# Sheet1.net
KiCad netlist of a schematic drawn in Altium Designer
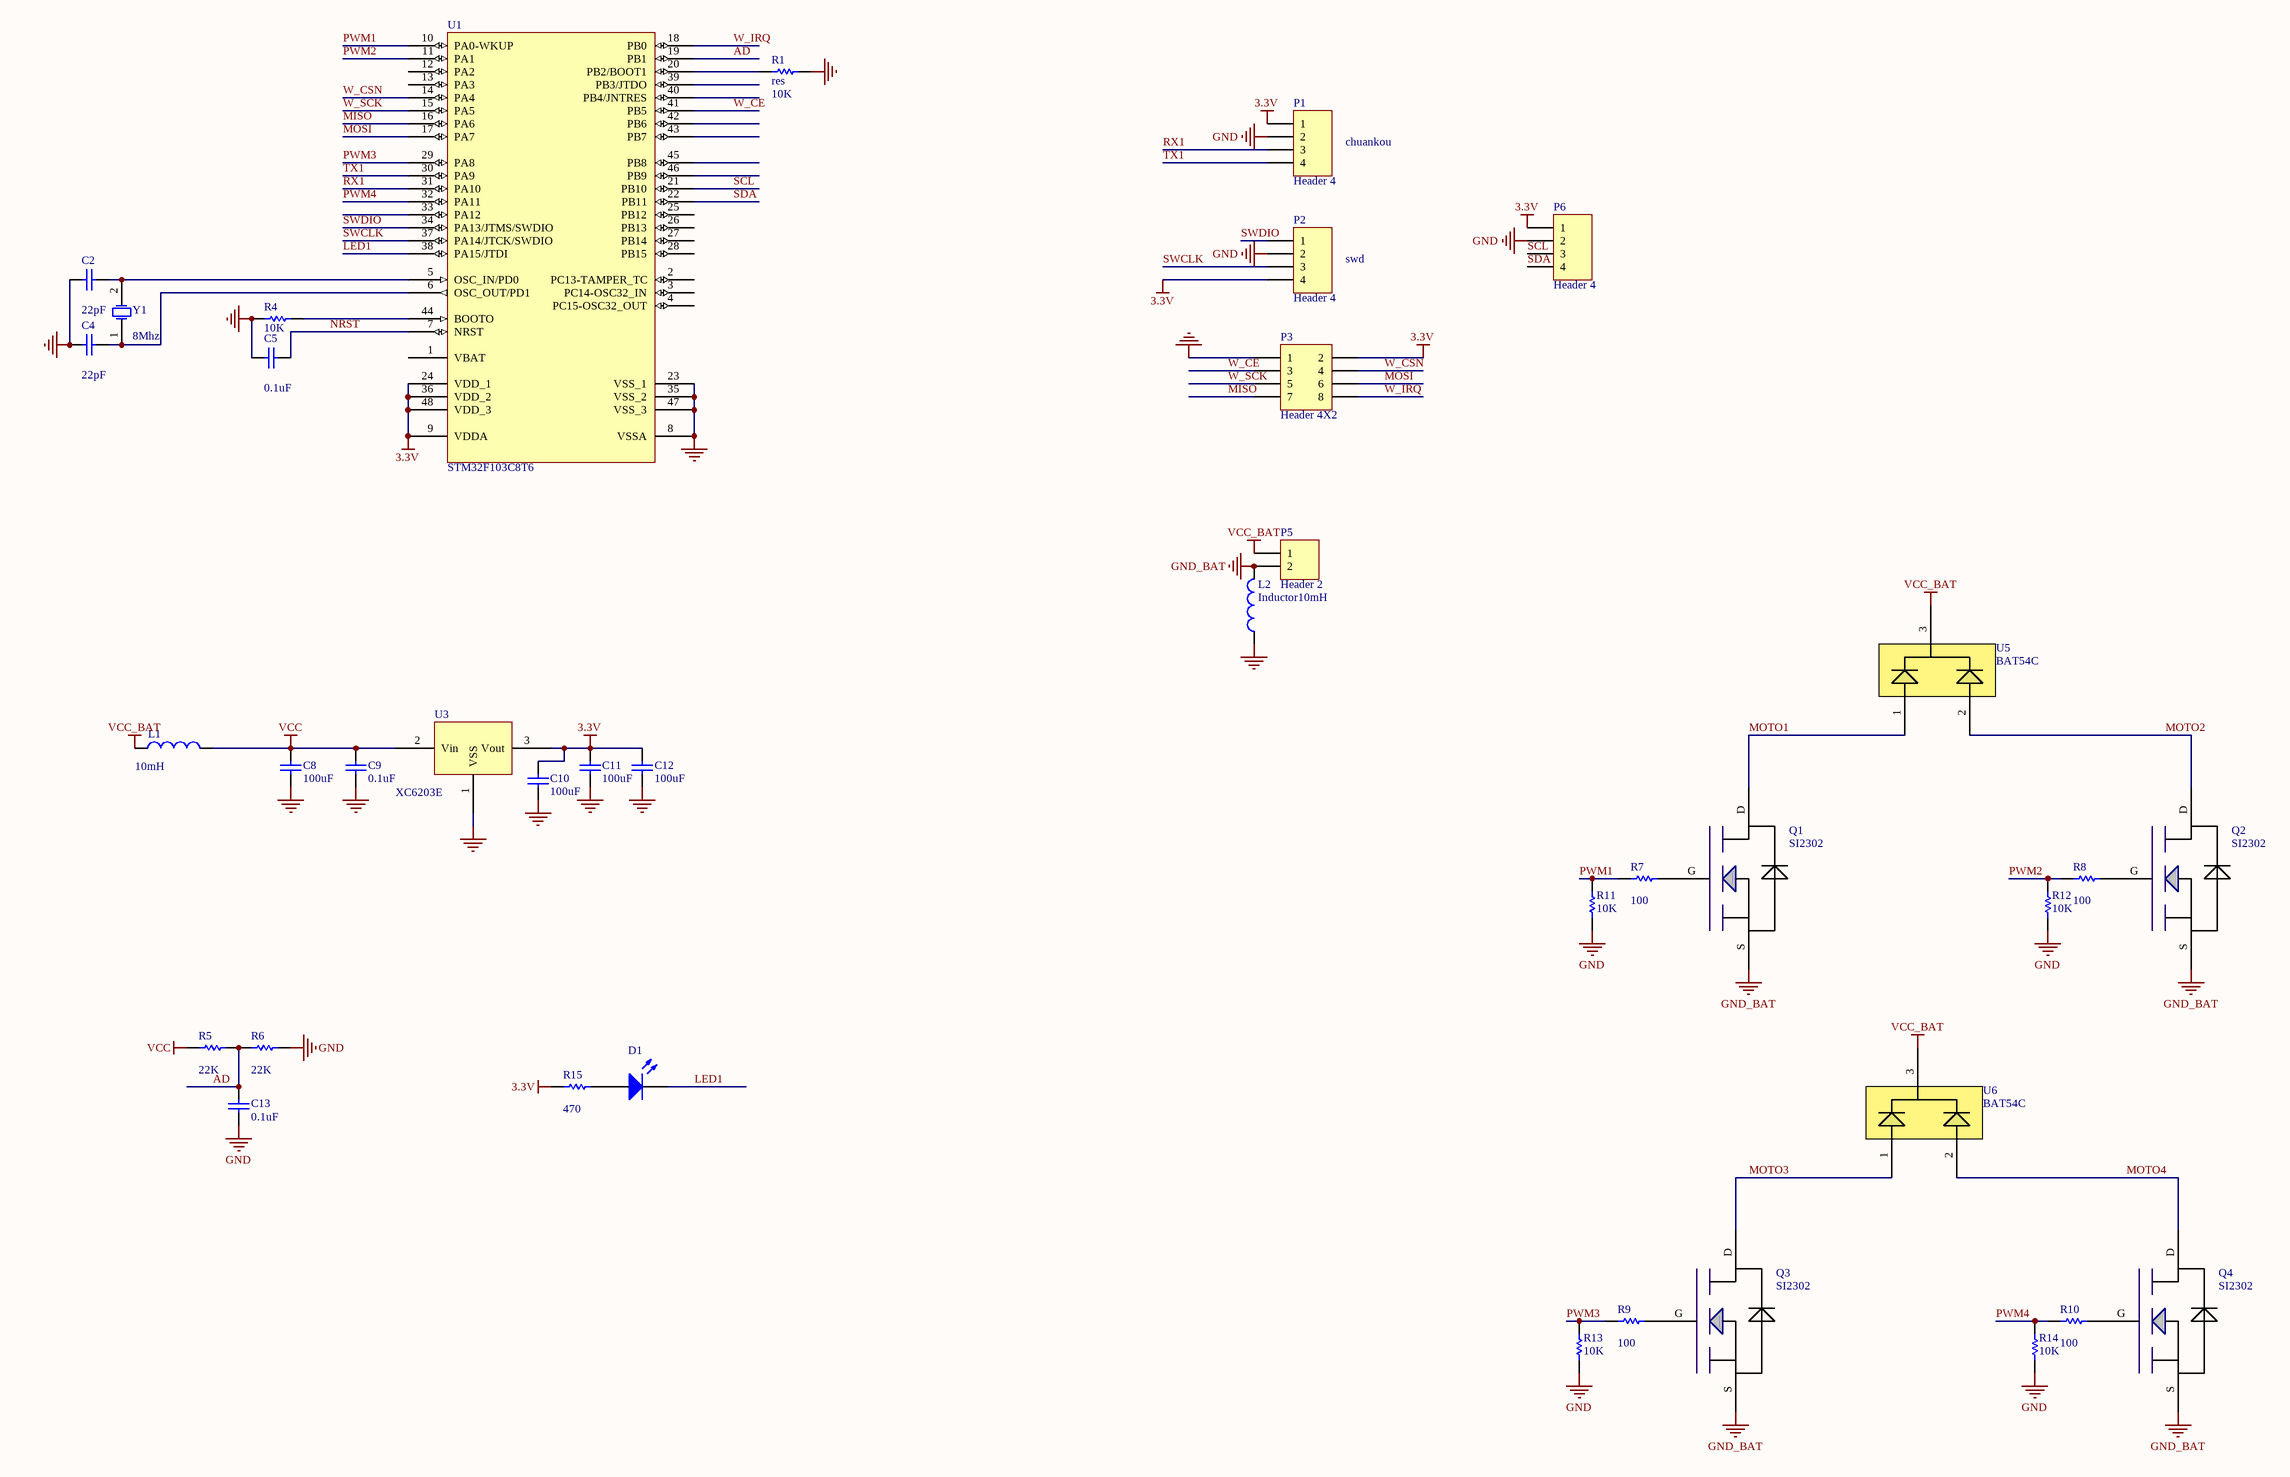
[diagram p0: Sheet1.SchDoc]

(export (version "E")
  (design (tool "Eeschema 10.0.6"))
  (components
    (comp (ref "C2")
      (value "22pF")
      (footprint "0603")
      (fields (field (name "Comment") "cap"))
      (libsource (lib "bai") (part "cap"))
    )
    (comp (ref "C4")
      (value "22pF")
      (footprint "0603")
      (fields (field (name "Comment") "cap"))
      (libsource (lib "bai") (part "cap"))
    )
    (comp (ref "C5")
      (value "0.1uF")
      (footprint "0603")
      (fields (field (name "Comment") "cap"))
      (libsource (lib "bai") (part "cap"))
    )
    (comp (ref "C8")
      (value "100uF")
      (footprint "0603")
      (fields (field (name "Comment") "cap"))
      (libsource (lib "bai") (part "cap"))
    )
    (comp (ref "C9")
      (value "0.1uF")
      (footprint "0603")
      (fields (field (name "Comment") "cap"))
      (libsource (lib "bai") (part "cap"))
    )
    (comp (ref "C10")
      (value "100uF")
      (footprint "0603")
      (fields (field (name "Comment") "cap"))
      (libsource (lib "bai") (part "cap"))
    )
    (comp (ref "C11")
      (value "100uF")
      (footprint "0603")
      (fields (field (name "Comment") "cap"))
      (libsource (lib "bai") (part "cap"))
    )
    (comp (ref "C12")
      (value "100uF")
      (footprint "0603")
      (fields (field (name "Comment") "cap"))
      (libsource (lib "bai") (part "cap"))
    )
    (comp (ref "C13")
      (value "0.1uF")
      (footprint "0603")
      (fields (field (name "Comment") "cap"))
      (libsource (lib "bai") (part "cap"))
    )
    (comp (ref "D1")
      (value "LED0")
      (footprint "0805")
      (description "Typical INFRARED GaAs LED")
      (fields (field (name "PUBLISHER") "Altium Limited"))
      (libsource (lib "Miscellaneous Devices") (part "LED0"))
    )
    (comp (ref "L1")
      (value "10mH")
      (footprint "0805")
      (fields (field (name "Comment") "Inductor"))
      (libsource (lib "bai") (part "Inductor"))
    )
    (comp (ref "L2") (value "Inductor10mH") (footprint "0805") (libsource (lib "bai") (part "Inductor")))
    (comp (ref "P1")
      (value "Header 4")
      (footprint "HDR1X4")
      (description "Header, 4-Pin")
      (fields (field (name "PUBLISHER") "Altium Limited"))
      (libsource (lib "Miscellaneous Connectors") (part "Header 4"))
    )
    (comp (ref "P2")
      (value "Header 4")
      (footprint "HDR1X4")
      (description "Header, 4-Pin")
      (fields (field (name "PUBLISHER") "Altium Limited"))
      (libsource (lib "Miscellaneous Connectors") (part "Header 4"))
    )
    (comp (ref "P3")
      (value "Header 4X2")
      (footprint "HDR2X4")
      (description "Header, 4-Pin, Dual row")
      (fields (field (name "PUBLISHER") "Altium Limited"))
      (libsource (lib "Miscellaneous Connectors") (part "Header 4X2"))
    )
    (comp (ref "P5")
      (value "Header 2")
      (footprint "HDR1X2")
      (description "Header, 2-Pin")
      (fields (field (name "PUBLISHER") "Altium Limited"))
      (libsource (lib "Miscellaneous Connectors") (part "Header 2"))
    )
    (comp (ref "P6")
      (value "Header 4")
      (footprint "HDR1X4")
      (description "Header, 4-Pin")
      (fields (field (name "PUBLISHER") "Altium Limited"))
      (libsource (lib "Miscellaneous Connectors") (part "Header 4"))
    )
    (comp (ref "Q1") (value "SI2302") (footprint "SOT-23") (libsource (lib "bai") (part "SI2302")))
    (comp (ref "Q2") (value "SI2302") (footprint "SOT-23") (libsource (lib "bai") (part "SI2302")))
    (comp (ref "Q3") (value "SI2302") (footprint "SOT-23") (libsource (lib "bai") (part "SI2302")))
    (comp (ref "Q4") (value "SI2302") (footprint "SOT-23") (libsource (lib "bai") (part "SI2302")))
    (comp (ref "R1")
      (value "res")
      (footprint "0603")
      (fields (field (name "RES") "10K"))
      (libsource (lib "bai") (part "res"))
    )
    (comp (ref "R4")
      (value "res")
      (footprint "0603")
      (fields (field (name "RES") "10K"))
      (libsource (lib "bai") (part "res"))
    )
    (comp (ref "R5")
      (value "res")
      (footprint "0603")
      (fields (field (name "RES") "22K"))
      (libsource (lib "bai") (part "res"))
    )
    (comp (ref "R6")
      (value "res")
      (footprint "0603")
      (fields (field (name "RES") "22K"))
      (libsource (lib "bai") (part "res"))
    )
    (comp (ref "R7")
      (value "res")
      (footprint "0603")
      (fields (field (name "RES") "100"))
      (libsource (lib "bai") (part "res"))
    )
    (comp (ref "R8")
      (value "res")
      (footprint "0603")
      (fields (field (name "RES") "100"))
      (libsource (lib "bai") (part "res"))
    )
    (comp (ref "R9")
      (value "res")
      (footprint "0603")
      (fields (field (name "RES") "100"))
      (libsource (lib "bai") (part "res"))
    )
    (comp (ref "R10")
      (value "res")
      (footprint "0603")
      (fields (field (name "RES") "100"))
      (libsource (lib "bai") (part "res"))
    )
    (comp (ref "R11")
      (value "res")
      (footprint "0603")
      (fields (field (name "RES") "10K"))
      (libsource (lib "bai") (part "res"))
    )
    (comp (ref "R12")
      (value "res")
      (footprint "0603")
      (fields (field (name "RES") "10K"))
      (libsource (lib "bai") (part "res"))
    )
    (comp (ref "R13")
      (value "res")
      (footprint "0603")
      (fields (field (name "RES") "10K"))
      (libsource (lib "bai") (part "res"))
    )
    (comp (ref "R14")
      (value "res")
      (footprint "0603")
      (fields (field (name "RES") "10K"))
      (libsource (lib "bai") (part "res"))
    )
    (comp (ref "R15")
      (value "res")
      (footprint "0603")
      (fields (field (name "RES") "470"))
      (libsource (lib "bai") (part "res"))
    )
    (comp (ref "U1")
      (value "STM32F103C8T6")
      (footprint "LQFP48S")
      (libsource (lib "bai") (part "STM32F103C8T6"))
    )
    (comp (ref "U3") (value "XC6203E") (footprint "SOT-89") (libsource (lib "文哥做的") (part "XC6203")))
    (comp (ref "U5") (value "BAT54C") (footprint "SOT-23") (libsource (lib "bai") (part "BAT54C")))
    (comp (ref "U6") (value "BAT54C") (footprint "SOT-23") (libsource (lib "bai") (part "BAT54C")))
    (comp (ref "Y1")
      (value "5032xtal")
      (footprint "XTAL")
      (fields (field (name "ALTIUM_UNNAMED_1") "8Mhz"))
      (libsource (lib "bai") (part "5032xtal"))
    )
  )
  (nets
    (net (code "1") (name "/AD") (class "Default")
      (node (ref "C13") (pin "2") (pinfunction "2_2") (pintype "passive"))
      (node (ref "R5") (pin "2") (pinfunction "2_2") (pintype "passive"))
      (node (ref "R6") (pin "1") (pinfunction "1_1") (pintype "passive"))
      (node (ref "U1") (pin "19") (pinfunction "PB1_19") (pintype "bidirectional"))
    )
    (net (code "2") (name "/LED1") (class "Default")
      (node (ref "D1") (pin "2") (pinfunction "K_2") (pintype "passive"))
      (node (ref "U1") (pin "38") (pinfunction "PA15/JTDI_38") (pintype "bidirectional"))
    )
    (net (code "3") (name "/MISO") (class "Default")
      (node (ref "P3") (pin "7") (pinfunction "7_7") (pintype "passive"))
      (node (ref "U1") (pin "16") (pinfunction "PA6_16") (pintype "bidirectional"))
    )
    (net (code "4") (name "/MOSI") (class "Default")
      (node (ref "P3") (pin "6") (pinfunction "6_6") (pintype "passive"))
      (node (ref "U1") (pin "17") (pinfunction "PA7_17") (pintype "bidirectional"))
    )
    (net (code "5") (name "/MOTO1") (class "Default")
      (node (ref "Q1") (pin "D") (pinfunction "3_D") (pintype "passive"))
      (node (ref "U5") (pin "1") (pinfunction "4_1") (pintype "passive"))
    )
    (net (code "6") (name "/MOTO2") (class "Default")
      (node (ref "Q2") (pin "D") (pinfunction "3_D") (pintype "passive"))
      (node (ref "U5") (pin "2") (pinfunction "5_2") (pintype "passive"))
    )
    (net (code "7") (name "/MOTO3") (class "Default")
      (node (ref "Q3") (pin "D") (pinfunction "3_D") (pintype "passive"))
      (node (ref "U6") (pin "1") (pinfunction "4_1") (pintype "passive"))
    )
    (net (code "8") (name "/MOTO4") (class "Default")
      (node (ref "Q4") (pin "D") (pinfunction "3_D") (pintype "passive"))
      (node (ref "U6") (pin "2") (pinfunction "5_2") (pintype "passive"))
    )
    (net (code "9") (name "/NRST") (class "Default")
      (node (ref "C5") (pin "2") (pinfunction "2_2") (pintype "passive"))
      (node (ref "U1") (pin "7") (pinfunction "NRST_7") (pintype "bidirectional"))
    )
    (net (code "10") (name "/PWM1") (class "Default")
      (node (ref "R11") (pin "2") (pinfunction "2_2") (pintype "passive"))
      (node (ref "R7") (pin "1") (pinfunction "1_1") (pintype "passive"))
      (node (ref "U1") (pin "10") (pinfunction "PA0-WKUP_10") (pintype "bidirectional"))
    )
    (net (code "11") (name "/PWM2") (class "Default")
      (node (ref "R12") (pin "2") (pinfunction "2_2") (pintype "passive"))
      (node (ref "R8") (pin "1") (pinfunction "1_1") (pintype "passive"))
      (node (ref "U1") (pin "11") (pinfunction "PA1_11") (pintype "bidirectional"))
    )
    (net (code "12") (name "/PWM3") (class "Default")
      (node (ref "R13") (pin "2") (pinfunction "2_2") (pintype "passive"))
      (node (ref "R9") (pin "1") (pinfunction "1_1") (pintype "passive"))
      (node (ref "U1") (pin "29") (pinfunction "PA8_29") (pintype "bidirectional"))
    )
    (net (code "13") (name "/PWM4") (class "Default")
      (node (ref "R10") (pin "1") (pinfunction "1_1") (pintype "passive"))
      (node (ref "R14") (pin "2") (pinfunction "2_2") (pintype "passive"))
      (node (ref "U1") (pin "32") (pinfunction "PA11_32") (pintype "bidirectional"))
    )
    (net (code "14") (name "/RX1") (class "Default")
      (node (ref "P1") (pin "3") (pinfunction "3_3") (pintype "passive"))
      (node (ref "U1") (pin "31") (pinfunction "PA10_31") (pintype "bidirectional"))
    )
    (net (code "15") (name "/SCL") (class "Default")
      (node (ref "P6") (pin "3") (pinfunction "3_3") (pintype "passive"))
      (node (ref "U1") (pin "21") (pinfunction "PB10_21") (pintype "bidirectional"))
    )
    (net (code "16") (name "/SDA") (class "Default")
      (node (ref "P6") (pin "4") (pinfunction "4_4") (pintype "passive"))
      (node (ref "U1") (pin "22") (pinfunction "PB11_22") (pintype "bidirectional"))
    )
    (net (code "17") (name "/SWCLK") (class "Default")
      (node (ref "P2") (pin "3") (pinfunction "3_3") (pintype "passive"))
      (node (ref "U1") (pin "37") (pinfunction "PA14/JTCK/SWDIO_37") (pintype "bidirectional"))
    )
    (net (code "18") (name "/SWDIO") (class "Default")
      (node (ref "P2") (pin "1") (pinfunction "1_1") (pintype "passive"))
      (node (ref "U1") (pin "34") (pinfunction "PA13/JTMS/SWDIO_34") (pintype "bidirectional"))
    )
    (net (code "19") (name "/TX1") (class "Default")
      (node (ref "P1") (pin "4") (pinfunction "4_4") (pintype "passive"))
      (node (ref "U1") (pin "30") (pinfunction "PA9_30") (pintype "bidirectional"))
    )
    (net (code "20") (name "/W_CE") (class "Default")
      (node (ref "P3") (pin "3") (pinfunction "3_3") (pintype "passive"))
      (node (ref "U1") (pin "41") (pinfunction "PB5_41") (pintype "bidirectional"))
    )
    (net (code "21") (name "/W_CSN") (class "Default")
      (node (ref "P3") (pin "4") (pinfunction "4_4") (pintype "passive"))
      (node (ref "U1") (pin "14") (pinfunction "PA4_14") (pintype "bidirectional"))
    )
    (net (code "22") (name "/W_IRQ") (class "Default")
      (node (ref "P3") (pin "8") (pinfunction "8_8") (pintype "passive"))
      (node (ref "U1") (pin "18") (pinfunction "PB0_18") (pintype "bidirectional"))
    )
    (net (code "23") (name "/W_SCK") (class "Default")
      (node (ref "P3") (pin "5") (pinfunction "5_5") (pintype "passive"))
      (node (ref "U1") (pin "15") (pinfunction "PA5_15") (pintype "bidirectional"))
    )
    (net (code "24") (name "3.3V") (class "Default")
      (node (ref "C10") (pin "2") (pinfunction "2_2") (pintype "passive"))
      (node (ref "C11") (pin "2") (pinfunction "2_2") (pintype "passive"))
      (node (ref "C12") (pin "2") (pinfunction "2_2") (pintype "passive"))
      (node (ref "P1") (pin "1") (pinfunction "1_1") (pintype "passive"))
      (node (ref "P2") (pin "4") (pinfunction "4_4") (pintype "passive"))
      (node (ref "P3") (pin "2") (pinfunction "2_2") (pintype "passive"))
      (node (ref "P6") (pin "1") (pinfunction "1_1") (pintype "passive"))
      (node (ref "R15") (pin "1") (pinfunction "1_1") (pintype "passive"))
      (node (ref "U1") (pin "24") (pinfunction "VDD_1_24") (pintype "passive"))
      (node (ref "U1") (pin "36") (pinfunction "VDD_2_36") (pintype "passive"))
      (node (ref "U1") (pin "48") (pinfunction "VDD_3_48") (pintype "passive"))
      (node (ref "U1") (pin "9") (pinfunction "VDDA_9") (pintype "passive"))
      (node (ref "U3") (pin "3") (pinfunction "Vout_3") (pintype "passive"))
    )
    (net (code "25") (name "GND") (class "Default")
      (node (ref "C10") (pin "1") (pinfunction "1_1") (pintype "passive"))
      (node (ref "C11") (pin "1") (pinfunction "1_1") (pintype "passive"))
      (node (ref "C12") (pin "1") (pinfunction "1_1") (pintype "passive"))
      (node (ref "C13") (pin "1") (pinfunction "1_1") (pintype "passive"))
      (node (ref "C2") (pin "1") (pinfunction "1_1") (pintype "passive"))
      (node (ref "C4") (pin "1") (pinfunction "1_1") (pintype "passive"))
      (node (ref "C5") (pin "1") (pinfunction "1_1") (pintype "passive"))
      (node (ref "C8") (pin "1") (pinfunction "1_1") (pintype "passive"))
      (node (ref "C9") (pin "1") (pinfunction "1_1") (pintype "passive"))
      (node (ref "L2") (pin "1") (pinfunction "1_1") (pintype "passive"))
      (node (ref "P1") (pin "2") (pinfunction "2_2") (pintype "passive"))
      (node (ref "P2") (pin "2") (pinfunction "2_2") (pintype "passive"))
      (node (ref "P3") (pin "1") (pinfunction "1_1") (pintype "passive"))
      (node (ref "P6") (pin "2") (pinfunction "2_2") (pintype "passive"))
      (node (ref "R1") (pin "2") (pinfunction "2_2") (pintype "passive"))
      (node (ref "R11") (pin "1") (pinfunction "1_1") (pintype "passive"))
      (node (ref "R12") (pin "1") (pinfunction "1_1") (pintype "passive"))
      (node (ref "R13") (pin "1") (pinfunction "1_1") (pintype "passive"))
      (node (ref "R14") (pin "1") (pinfunction "1_1") (pintype "passive"))
      (node (ref "R4") (pin "1") (pinfunction "1_1") (pintype "passive"))
      (node (ref "R6") (pin "2") (pinfunction "2_2") (pintype "passive"))
      (node (ref "U1") (pin "23") (pinfunction "VSS_1_23") (pintype "passive"))
      (node (ref "U1") (pin "35") (pinfunction "VSS_2_35") (pintype "passive"))
      (node (ref "U1") (pin "47") (pinfunction "VSS_3_47") (pintype "passive"))
      (node (ref "U1") (pin "8") (pinfunction "VSSA_8") (pintype "passive"))
      (node (ref "U3") (pin "1") (pinfunction "VSS_1") (pintype "passive"))
    )
    (net (code "26") (name "GND_BAT") (class "Default")
      (node (ref "L2") (pin "2") (pinfunction "2_2") (pintype "passive"))
      (node (ref "P5") (pin "2") (pinfunction "2_2") (pintype "passive"))
      (node (ref "Q1") (pin "S") (pinfunction "2_S") (pintype "passive"))
      (node (ref "Q2") (pin "S") (pinfunction "2_S") (pintype "passive"))
      (node (ref "Q3") (pin "S") (pinfunction "2_S") (pintype "passive"))
      (node (ref "Q4") (pin "S") (pinfunction "2_S") (pintype "passive"))
    )
    (net (code "27") (name "Net-(D1-A)") (class "Default")
      (node (ref "D1") (pin "1") (pinfunction "A_1") (pintype "passive"))
      (node (ref "R15") (pin "2") (pinfunction "2_2") (pintype "passive"))
    )
    (net (code "28") (name "Net-(Q1-PadG)") (class "Default")
      (node (ref "Q1") (pin "G") (pinfunction "G_G") (pintype "passive"))
      (node (ref "R7") (pin "2") (pinfunction "2_2") (pintype "passive"))
    )
    (net (code "29") (name "Net-(Q2-PadG)") (class "Default")
      (node (ref "Q2") (pin "G") (pinfunction "G_G") (pintype "passive"))
      (node (ref "R8") (pin "2") (pinfunction "2_2") (pintype "passive"))
    )
    (net (code "30") (name "Net-(Q3-PadG)") (class "Default")
      (node (ref "Q3") (pin "G") (pinfunction "G_G") (pintype "passive"))
      (node (ref "R9") (pin "2") (pinfunction "2_2") (pintype "passive"))
    )
    (net (code "31") (name "Net-(Q4-PadG)") (class "Default")
      (node (ref "Q4") (pin "G") (pinfunction "G_G") (pintype "passive"))
      (node (ref "R10") (pin "2") (pinfunction "2_2") (pintype "passive"))
    )
    (net (code "32") (name "Net-(U1-BOOTO)") (class "Default")
      (node (ref "R4") (pin "2") (pinfunction "2_2") (pintype "passive"))
      (node (ref "U1") (pin "44") (pinfunction "BOOTO_44") (pintype "input"))
    )
    (net (code "33") (name "Net-(U1-OSC_IN{slash}PD0)") (class "Default")
      (node (ref "C2") (pin "2") (pinfunction "2_2") (pintype "passive"))
      (node (ref "U1") (pin "5") (pinfunction "OSC_IN/PD0_5") (pintype "input"))
      (node (ref "Y1") (pin "2") (pinfunction "OSC2_2") (pintype "passive"))
    )
    (net (code "34") (name "Net-(U1-OSC_OUT{slash}PD1)") (class "Default")
      (node (ref "C4") (pin "2") (pinfunction "2_2") (pintype "passive"))
      (node (ref "U1") (pin "6") (pinfunction "OSC_OUT/PD1_6") (pintype "output"))
      (node (ref "Y1") (pin "1") (pinfunction "OSC1_1") (pintype "passive"))
    )
    (net (code "35") (name "Net-(U1-PB2{slash}BOOT1)") (class "Default")
      (node (ref "R1") (pin "1") (pinfunction "1_1") (pintype "passive"))
      (node (ref "U1") (pin "20") (pinfunction "PB2/BOOT1_20") (pintype "bidirectional"))
    )
    (net (code "36") (name "VCC") (class "Default")
      (node (ref "C8") (pin "2") (pinfunction "2_2") (pintype "passive"))
      (node (ref "C9") (pin "2") (pinfunction "2_2") (pintype "passive"))
      (node (ref "L1") (pin "2") (pinfunction "2_2") (pintype "passive"))
      (node (ref "R5") (pin "1") (pinfunction "1_1") (pintype "passive"))
      (node (ref "U3") (pin "2") (pinfunction "Vin_2") (pintype "passive"))
    )
    (net (code "37") (name "VCC_BAT") (class "Default")
      (node (ref "L1") (pin "1") (pinfunction "1_1") (pintype "passive"))
      (node (ref "P5") (pin "1") (pinfunction "1_1") (pintype "passive"))
      (node (ref "U5") (pin "3") (pinfunction "0_3") (pintype "passive"))
      (node (ref "U6") (pin "3") (pinfunction "0_3") (pintype "passive"))
    )
    (net (code "38") (name "unconnected-(U1-PA2-Pad12)") (class "Default")
      (node (ref "U1") (pin "12") (pinfunction "PA2_12") (pintype "bidirectional"))
    )
    (net (code "39") (name "unconnected-(U1-PA3-Pad13)") (class "Default")
      (node (ref "U1") (pin "13") (pinfunction "PA3_13") (pintype "bidirectional"))
    )
    (net (code "40") (name "unconnected-(U1-PA12-Pad33)") (class "Default")
      (node (ref "U1") (pin "33") (pinfunction "PA12_33") (pintype "bidirectional"))
    )
    (net (code "41") (name "unconnected-(U1-PB3{slash}JTDO-Pad39)") (class "Default")
      (node (ref "U1") (pin "39") (pinfunction "PB3/JTDO_39") (pintype "bidirectional"))
    )
    (net (code "42") (name "unconnected-(U1-PB4{slash}JNTRES-Pad40)") (class "Default")
      (node (ref "U1") (pin "40") (pinfunction "PB4/JNTRES_40") (pintype "bidirectional"))
    )
    (net (code "43") (name "unconnected-(U1-PB6-Pad42)") (class "Default")
      (node (ref "U1") (pin "42") (pinfunction "PB6_42") (pintype "bidirectional"))
    )
    (net (code "44") (name "unconnected-(U1-PB7-Pad43)") (class "Default")
      (node (ref "U1") (pin "43") (pinfunction "PB7_43") (pintype "bidirectional"))
    )
    (net (code "45") (name "unconnected-(U1-PB8-Pad45)") (class "Default")
      (node (ref "U1") (pin "45") (pinfunction "PB8_45") (pintype "bidirectional"))
    )
    (net (code "46") (name "unconnected-(U1-PB9-Pad46)") (class "Default")
      (node (ref "U1") (pin "46") (pinfunction "PB9_46") (pintype "bidirectional"))
    )
    (net (code "47") (name "unconnected-(U1-PB12-Pad25)") (class "Default")
      (node (ref "U1") (pin "25") (pinfunction "PB12_25") (pintype "bidirectional"))
    )
    (net (code "48") (name "unconnected-(U1-PB13-Pad26)") (class "Default")
      (node (ref "U1") (pin "26") (pinfunction "PB13_26") (pintype "bidirectional"))
    )
    (net (code "49") (name "unconnected-(U1-PB14-Pad27)") (class "Default")
      (node (ref "U1") (pin "27") (pinfunction "PB14_27") (pintype "bidirectional"))
    )
    (net (code "50") (name "unconnected-(U1-PB15-Pad28)") (class "Default")
      (node (ref "U1") (pin "28") (pinfunction "PB15_28") (pintype "bidirectional"))
    )
    (net (code "51") (name "unconnected-(U1-PC13-TAMPER_TC-Pad2)") (class "Default")
      (node (ref "U1") (pin "2") (pinfunction "PC13-TAMPER_TC_2") (pintype "bidirectional"))
    )
    (net (code "52") (name "unconnected-(U1-PC14-OSC32_IN-Pad3)") (class "Default")
      (node (ref "U1") (pin "3") (pinfunction "PC14-OSC32_IN_3") (pintype "bidirectional"))
    )
    (net (code "53") (name "unconnected-(U1-PC15-OSC32_OUT-Pad4)") (class "Default")
      (node (ref "U1") (pin "4") (pinfunction "PC15-OSC32_OUT_4") (pintype "bidirectional"))
    )
    (net (code "54") (name "unconnected-(U1-VBAT-Pad1)") (class "Default")
      (node (ref "U1") (pin "1") (pinfunction "VBAT_1") (pintype "passive"))
    )
  )
)
